# All_Dreery_Diorth_CE.net
KiCad netlist of a schematic drawn in EAGLE
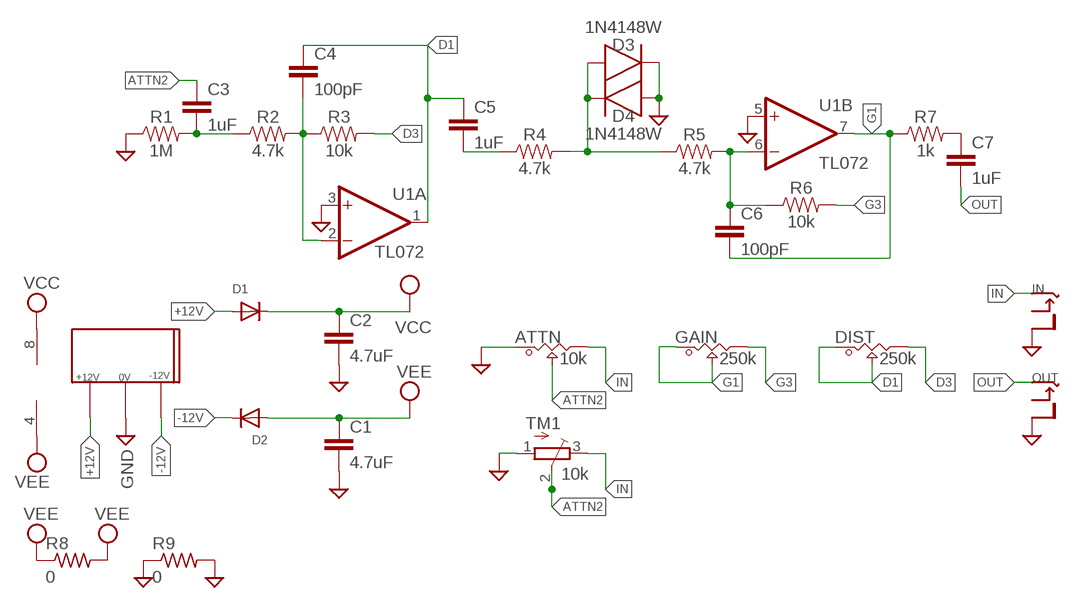
[diagram p0: schematic, sheet 1]

(export (version "E")
  (design (tool "Eeschema 10.0.6"))
  (components
    (comp (ref "ATTN")
      (value "10k")
      (footprint "eagle-import:POT_9MM_SMD")
      (libsource (lib "eagle-import") (part "POT_9MM_SMD"))
    )
    (comp (ref "C1")
      (value "4.7uF")
      (footprint "eagle-import:1206")
      (libsource (lib "eagle-import") (part "4.7UF-1206-16V-(+80/-20%)"))
    )
    (comp (ref "C2")
      (value "4.7uF")
      (footprint "eagle-import:1206")
      (libsource (lib "eagle-import") (part "4.7UF-1206-16V-(+80/-20%)"))
    )
    (comp (ref "C3")
      (value "1uF")
      (footprint "eagle-import:0603")
      (libsource (lib "eagle-import") (part "0.1UF-0603-25V-5%"))
    )
    (comp (ref "C4")
      (value "100pF")
      (footprint "eagle-import:0603")
      (libsource (lib "eagle-import") (part "0.1UF-0603-25V-5%"))
    )
    (comp (ref "C5")
      (value "1uF")
      (footprint "eagle-import:0603")
      (libsource (lib "eagle-import") (part "0.1UF-0603-25V-5%"))
    )
    (comp (ref "C6")
      (value "100pF")
      (footprint "eagle-import:0603")
      (libsource (lib "eagle-import") (part "0.1UF-0603-25V-5%"))
    )
    (comp (ref "C7")
      (value "1uF")
      (footprint "eagle-import:0603")
      (libsource (lib "eagle-import") (part "0.1UF-0603-25V-5%"))
    )
    (comp (ref "D1")
      (value "DIODESOD-123")
      (footprint "eagle-import:SOD-123")
      (libsource (lib "eagle-import") (part "DIODESOD-123"))
    )
    (comp (ref "D2")
      (value "DIODESOD-123")
      (footprint "eagle-import:SOD-123")
      (libsource (lib "eagle-import") (part "DIODESOD-123"))
    )
    (comp (ref "D3")
      (value "1N4148W")
      (footprint "eagle-import:SOD3715X135")
      (fields (field (name "MANUFACTURER") "Diodes Incorporated"))
      (libsource (lib "eagle-import") (part "DIODE__SOD123G1N4148W-7-F"))
    )
    (comp (ref "D4")
      (value "1N4148W")
      (footprint "eagle-import:SOD3715X135")
      (fields (field (name "MANUFACTURER") "Diodes Incorporated"))
      (libsource (lib "eagle-import") (part "DIODE__SOD123G1N4148W-7-F"))
    )
    (comp (ref "DIST")
      (value "250k")
      (footprint "eagle-import:POT_9MM_SMD")
      (libsource (lib "eagle-import") (part "POT_9MM_SMD"))
    )
    (comp (ref "GAIN")
      (value "250k")
      (footprint "eagle-import:POT_9MM_SMD")
      (libsource (lib "eagle-import") (part "POT_9MM_SMD"))
    )
    (comp (ref "R1")
      (value "1M")
      (footprint "eagle-import:0603")
      (libsource (lib "eagle-import") (part "RESISTOR0603"))
    )
    (comp (ref "R2")
      (value "4.7k")
      (footprint "eagle-import:0603")
      (libsource (lib "eagle-import") (part "RESISTOR0603"))
    )
    (comp (ref "R3")
      (value "10k")
      (footprint "eagle-import:0603")
      (libsource (lib "eagle-import") (part "RESISTOR0603"))
    )
    (comp (ref "R4")
      (value "4.7k")
      (footprint "eagle-import:0603")
      (libsource (lib "eagle-import") (part "RESISTOR0603"))
    )
    (comp (ref "R5")
      (value "4.7k")
      (footprint "eagle-import:0603")
      (libsource (lib "eagle-import") (part "RESISTOR0603"))
    )
    (comp (ref "R6")
      (value "10k")
      (footprint "eagle-import:0603")
      (libsource (lib "eagle-import") (part "RESISTOR0603"))
    )
    (comp (ref "R7")
      (value "1k")
      (footprint "eagle-import:0603")
      (libsource (lib "eagle-import") (part "RESISTOR0603"))
    )
    (comp (ref "R8")
      (value "0")
      (footprint "eagle-import:R0402")
      (libsource (lib "eagle-import") (part "R-US_R0402"))
    )
    (comp (ref "R9")
      (value "0")
      (footprint "eagle-import:R0402")
      (libsource (lib "eagle-import") (part "R-US_R0402"))
    )
    (comp (ref "TM1")
      (value "10k")
      (footprint "eagle-import:TC33X")
      (libsource (lib "eagle-import") (part "TRIMPOTTC33X"))
    )
    (comp (ref "U$1")
      (value "EURO_POW_CEH")
      (footprint "eagle-import:EURO_POW_CEH")
      (libsource (lib "eagle-import") (part "EURO_POW_CEH"))
    )
    (comp (ref "U$2")
      (value "THONKICONN_CE_2X_COMG_NOSW")
      (footprint "eagle-import:1.27MM_CE_2X_COMG_NOSW")
      (libsource (lib "eagle-import") (part "THONKICONN_CE_2X_COMG_NOSW"))
    )
    (comp (ref "U1")
      (value "TL072")
      (footprint "eagle-import:TSSOP-8")
      (libsource (lib "eagle-import") (part "TL072TSSOP"))
    )
  )
  (nets
    (net (code "1") (name "+12V") (class "Default")
      (node (ref "D1") (pin "A") (pinfunction "A_A") (pintype "passive"))
      (node (ref "U$1") (pin "+12V") (pinfunction "+12V_+12V") (pintype "bidirectional"))
    )
    (net (code "2") (name "-12V") (class "Default")
      (node (ref "D2") (pin "C") (pinfunction "C_C") (pintype "passive"))
      (node (ref "U$1") (pin "-12V") (pinfunction "-12V_-12V") (pintype "bidirectional"))
    )
    (net (code "3") (name "ATTN2") (class "Default")
      (node (ref "ATTN") (pin "2") (pinfunction "2_2") (pintype "bidirectional"))
      (node (ref "C3") (pin "1") (pinfunction "1_1") (pintype "passive"))
      (node (ref "TM1") (pin "2") (pinfunction "S_2") (pintype "passive"))
    )
    (net (code "4") (name "D1") (class "Default")
      (node (ref "C4") (pin "1") (pinfunction "1_1") (pintype "passive"))
      (node (ref "C5") (pin "1") (pinfunction "1_1") (pintype "passive"))
      (node (ref "DIST") (pin "1") (pinfunction "1_1") (pintype "bidirectional"))
      (node (ref "DIST") (pin "2") (pinfunction "2_2") (pintype "bidirectional"))
      (node (ref "U1") (pin "1") (pinfunction "OUT_1") (pintype "output"))
    )
    (net (code "5") (name "D3") (class "Default")
      (node (ref "DIST") (pin "3") (pinfunction "3_3") (pintype "bidirectional"))
      (node (ref "R3") (pin "2") (pinfunction "2_2") (pintype "passive"))
    )
    (net (code "6") (name "G1") (class "Default")
      (node (ref "C6") (pin "2") (pinfunction "2_2") (pintype "passive"))
      (node (ref "GAIN") (pin "1") (pinfunction "1_1") (pintype "bidirectional"))
      (node (ref "GAIN") (pin "2") (pinfunction "2_2") (pintype "bidirectional"))
      (node (ref "R7") (pin "1") (pinfunction "1_1") (pintype "passive"))
      (node (ref "U1") (pin "7") (pinfunction "OUT_7") (pintype "output"))
    )
    (net (code "7") (name "G3") (class "Default")
      (node (ref "GAIN") (pin "3") (pinfunction "3_3") (pintype "bidirectional"))
      (node (ref "R6") (pin "2") (pinfunction "2_2") (pintype "passive"))
    )
    (net (code "8") (name "GND") (class "Default")
      (node (ref "ATTN") (pin "1") (pinfunction "1_1") (pintype "bidirectional"))
      (node (ref "C1") (pin "2") (pinfunction "2_2") (pintype "passive"))
      (node (ref "C2") (pin "2") (pinfunction "2_2") (pintype "passive"))
      (node (ref "D3") (pin "1") (pinfunction "C_1") (pintype "passive"))
      (node (ref "D4") (pin "2") (pinfunction "A_2") (pintype "passive"))
      (node (ref "R1") (pin "1") (pinfunction "1_1") (pintype "passive"))
      (node (ref "R9") (pin "1") (pinfunction "1_1") (pintype "passive"))
      (node (ref "R9") (pin "2") (pinfunction "2_2") (pintype "passive"))
      (node (ref "TM1") (pin "1") (pinfunction "A_1") (pintype "passive"))
      (node (ref "U$1") (pin "GND") (pinfunction "GND_GND") (pintype "bidirectional"))
      (node (ref "U$2") (pin "0") (pinfunction "S_0") (pintype "bidirectional"))
      (node (ref "U1") (pin "3") (pinfunction "+IN_3") (pintype "input"))
      (node (ref "U1") (pin "5") (pinfunction "+IN_5") (pintype "input"))
    )
    (net (code "9") (name "IN") (class "Default")
      (node (ref "ATTN") (pin "3") (pinfunction "3_3") (pintype "bidirectional"))
      (node (ref "TM1") (pin "3") (pinfunction "E_3") (pintype "passive"))
      (node (ref "U$2") (pin "1") (pinfunction "T_1") (pintype "bidirectional"))
    )
    (net (code "10") (name "Net-(C3-Pad2)") (class "Default")
      (node (ref "C3") (pin "2") (pinfunction "2_2") (pintype "passive"))
      (node (ref "R1") (pin "2") (pinfunction "2_2") (pintype "passive"))
      (node (ref "R2") (pin "1") (pinfunction "1_1") (pintype "passive"))
    )
    (net (code "11") (name "Net-(C5-Pad2)") (class "Default")
      (node (ref "C5") (pin "2") (pinfunction "2_2") (pintype "passive"))
      (node (ref "R4") (pin "1") (pinfunction "1_1") (pintype "passive"))
    )
    (net (code "12") (name "Net-(C7-Pad1)") (class "Default")
      (node (ref "C7") (pin "1") (pinfunction "1_1") (pintype "passive"))
      (node (ref "R7") (pin "2") (pinfunction "2_2") (pintype "passive"))
    )
    (net (code "13") (name "Net-(D3-A)") (class "Default")
      (node (ref "D3") (pin "2") (pinfunction "A_2") (pintype "passive"))
      (node (ref "D4") (pin "1") (pinfunction "C_1") (pintype "passive"))
      (node (ref "R4") (pin "2") (pinfunction "2_2") (pintype "passive"))
      (node (ref "R5") (pin "1") (pinfunction "1_1") (pintype "passive"))
    )
    (net (code "14") (name "Net-(U1A--IN)") (class "Default")
      (node (ref "C4") (pin "2") (pinfunction "2_2") (pintype "passive"))
      (node (ref "R2") (pin "2") (pinfunction "2_2") (pintype "passive"))
      (node (ref "R3") (pin "1") (pinfunction "1_1") (pintype "passive"))
      (node (ref "U1") (pin "2") (pinfunction "-IN_2") (pintype "input"))
    )
    (net (code "15") (name "Net-(U1B--IN)") (class "Default")
      (node (ref "C6") (pin "1") (pinfunction "1_1") (pintype "passive"))
      (node (ref "R5") (pin "2") (pinfunction "2_2") (pintype "passive"))
      (node (ref "R6") (pin "1") (pinfunction "1_1") (pintype "passive"))
      (node (ref "U1") (pin "6") (pinfunction "-IN_6") (pintype "input"))
    )
    (net (code "16") (name "OUT") (class "Default")
      (node (ref "C7") (pin "2") (pinfunction "2_2") (pintype "passive"))
      (node (ref "U$2") (pin "2") (pinfunction "T_2") (pintype "bidirectional"))
    )
    (net (code "17") (name "VCC") (class "Default")
      (node (ref "C2") (pin "1") (pinfunction "1_1") (pintype "passive"))
      (node (ref "D1") (pin "C") (pinfunction "C_C") (pintype "passive"))
      (node (ref "U1") (pin "8") (pinfunction "V+_8") (pintype "power_in"))
    )
    (net (code "18") (name "VEE") (class "Default")
      (node (ref "C1") (pin "1") (pinfunction "1_1") (pintype "passive"))
      (node (ref "D2") (pin "A") (pinfunction "A_A") (pintype "passive"))
      (node (ref "R8") (pin "1") (pinfunction "1_1") (pintype "passive"))
      (node (ref "R8") (pin "2") (pinfunction "2_2") (pintype "passive"))
      (node (ref "U1") (pin "4") (pinfunction "V-_4") (pintype "power_in"))
    )
  )
)
